# Signal_Integrity_2L.net
KiCad netlist of a schematic drawn in Altium Designer
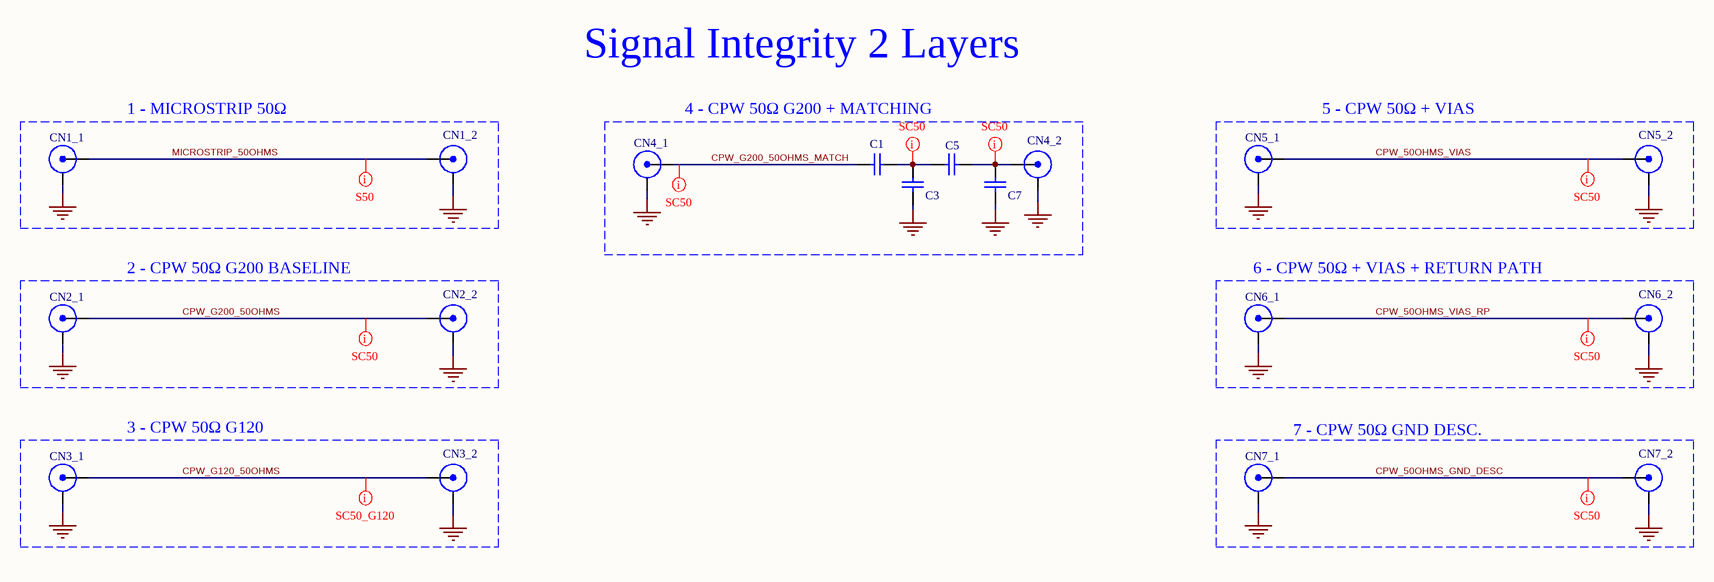
[diagram p0: Signal_Integrity_2L.SchDoc]

(export (version "E")
  (design (tool "Eeschema 10.0.6"))
  (components
    (comp (ref "C1")
      (value "CAP SMD 0402")
      (footprint "0402")
      (description "0402")
      (libsource (lib "Impedance") (part "CAP SMD 0402"))
    )
    (comp (ref "C3")
      (value "CAP SMD 0402")
      (footprint "0402")
      (description "0402")
      (libsource (lib "Impedance") (part "CAP SMD 0402"))
    )
    (comp (ref "C5")
      (value "CAP SMD 0402")
      (footprint "0402")
      (description "0402")
      (libsource (lib "Impedance") (part "CAP SMD 0402"))
    )
    (comp (ref "C7")
      (value "CAP SMD 0402")
      (footprint "0402")
      (description "0402")
      (libsource (lib "Impedance") (part "CAP SMD 0402"))
    )
    (comp (ref "CN1_1")
      (value "SMA-KE EDGE")
      (footprint "SMA-KE EDGE")
      (description "SMA Connector Receptacle, Female Socket 50Ohm Board Edge, End Launch Solder")
      (fields
        (field (name "MOUSER PART NUMBER") "712-CONSMA020.062-G")
        (field (name "MANUFACTURER_PART_NUMBER") "CONSMA020.062-G")
      )
      (libsource (lib "Impedance") (part "SMA-KE EDGE"))
    )
    (comp (ref "CN1_2")
      (value "SMA-KE EDGE")
      (footprint "SMA-KE EDGE")
      (description "SMA Connector Receptacle, Female Socket 50Ohm Board Edge, End Launch Solder")
      (fields
        (field (name "MOUSER PART NUMBER") "712-CONSMA020.062-G")
        (field (name "MANUFACTURER_PART_NUMBER") "CONSMA020.062-G")
      )
      (libsource (lib "Impedance") (part "SMA-KE EDGE"))
    )
    (comp (ref "CN2_1")
      (value "SMA-KE EDGE")
      (footprint "SMA-KE EDGE")
      (description "SMA Connector Receptacle, Female Socket 50Ohm Board Edge, End Launch Solder")
      (fields
        (field (name "MOUSER PART NUMBER") "712-CONSMA020.062-G")
        (field (name "MANUFACTURER_PART_NUMBER") "CONSMA020.062-G")
      )
      (libsource (lib "Impedance") (part "SMA-KE EDGE"))
    )
    (comp (ref "CN2_2")
      (value "SMA-KE EDGE")
      (footprint "SMA-KE EDGE")
      (description "SMA Connector Receptacle, Female Socket 50Ohm Board Edge, End Launch Solder")
      (fields
        (field (name "MOUSER PART NUMBER") "712-CONSMA020.062-G")
        (field (name "MANUFACTURER_PART_NUMBER") "CONSMA020.062-G")
      )
      (libsource (lib "Impedance") (part "SMA-KE EDGE"))
    )
    (comp (ref "CN3_1")
      (value "SMA-KE EDGE")
      (footprint "SMA-KE EDGE")
      (description "SMA Connector Receptacle, Female Socket 50Ohm Board Edge, End Launch Solder")
      (fields
        (field (name "MOUSER PART NUMBER") "712-CONSMA020.062-G")
        (field (name "MANUFACTURER_PART_NUMBER") "CONSMA020.062-G")
      )
      (libsource (lib "Impedance") (part "SMA-KE EDGE"))
    )
    (comp (ref "CN3_2")
      (value "SMA-KE EDGE")
      (footprint "SMA-KE EDGE")
      (description "SMA Connector Receptacle, Female Socket 50Ohm Board Edge, End Launch Solder")
      (fields
        (field (name "MOUSER PART NUMBER") "712-CONSMA020.062-G")
        (field (name "MANUFACTURER_PART_NUMBER") "CONSMA020.062-G")
      )
      (libsource (lib "Impedance") (part "SMA-KE EDGE"))
    )
    (comp (ref "CN4_1")
      (value "SMA-KE EDGE")
      (footprint "SMA-KE EDGE")
      (description "SMA Connector Receptacle, Female Socket 50Ohm Board Edge, End Launch Solder")
      (fields
        (field (name "MOUSER PART NUMBER") "712-CONSMA020.062-G")
        (field (name "MANUFACTURER_PART_NUMBER") "CONSMA020.062-G")
      )
      (libsource (lib "Impedance") (part "SMA-KE EDGE"))
    )
    (comp (ref "CN4_2")
      (value "SMA-KE EDGE")
      (footprint "SMA-KE EDGE")
      (description "SMA Connector Receptacle, Female Socket 50Ohm Board Edge, End Launch Solder")
      (fields
        (field (name "MOUSER PART NUMBER") "712-CONSMA020.062-G")
        (field (name "MANUFACTURER_PART_NUMBER") "CONSMA020.062-G")
      )
      (libsource (lib "Impedance") (part "SMA-KE EDGE"))
    )
    (comp (ref "CN5_1")
      (value "SMA-KE EDGE")
      (footprint "SMA-KE EDGE")
      (description "SMA Connector Receptacle, Female Socket 50Ohm Board Edge, End Launch Solder")
      (fields
        (field (name "MOUSER PART NUMBER") "712-CONSMA020.062-G")
        (field (name "MANUFACTURER_PART_NUMBER") "CONSMA020.062-G")
      )
      (libsource (lib "Impedance") (part "SMA-KE EDGE"))
    )
    (comp (ref "CN5_2")
      (value "SMA-KE EDGE")
      (footprint "SMA-KE EDGE")
      (description "SMA Connector Receptacle, Female Socket 50Ohm Board Edge, End Launch Solder")
      (fields
        (field (name "MOUSER PART NUMBER") "712-CONSMA020.062-G")
        (field (name "MANUFACTURER_PART_NUMBER") "CONSMA020.062-G")
      )
      (libsource (lib "Impedance") (part "SMA-KE EDGE"))
    )
    (comp (ref "CN6_1")
      (value "SMA-KE EDGE")
      (footprint "SMA-KE EDGE")
      (description "SMA Connector Receptacle, Female Socket 50Ohm Board Edge, End Launch Solder")
      (fields
        (field (name "MOUSER PART NUMBER") "712-CONSMA020.062-G")
        (field (name "MANUFACTURER_PART_NUMBER") "CONSMA020.062-G")
      )
      (libsource (lib "Impedance") (part "SMA-KE EDGE"))
    )
    (comp (ref "CN6_2")
      (value "SMA-KE EDGE")
      (footprint "SMA-KE EDGE")
      (description "SMA Connector Receptacle, Female Socket 50Ohm Board Edge, End Launch Solder")
      (fields
        (field (name "MOUSER PART NUMBER") "712-CONSMA020.062-G")
        (field (name "MANUFACTURER_PART_NUMBER") "CONSMA020.062-G")
      )
      (libsource (lib "Impedance") (part "SMA-KE EDGE"))
    )
    (comp (ref "CN7_1")
      (value "SMA-KE EDGE")
      (footprint "SMA-KE EDGE")
      (description "SMA Connector Receptacle, Female Socket 50Ohm Board Edge, End Launch Solder")
      (fields
        (field (name "MOUSER PART NUMBER") "712-CONSMA020.062-G")
        (field (name "MANUFACTURER_PART_NUMBER") "CONSMA020.062-G")
      )
      (libsource (lib "Impedance") (part "SMA-KE EDGE"))
    )
    (comp (ref "CN7_2")
      (value "SMA-KE EDGE")
      (footprint "SMA-KE EDGE")
      (description "SMA Connector Receptacle, Female Socket 50Ohm Board Edge, End Launch Solder")
      (fields
        (field (name "MOUSER PART NUMBER") "712-CONSMA020.062-G")
        (field (name "MANUFACTURER_PART_NUMBER") "CONSMA020.062-G")
      )
      (libsource (lib "Impedance") (part "SMA-KE EDGE"))
    )
  )
  (nets
    (net (code "1") (name "/CPW_50OHMS_GND_DESC") (class "Default")
      (node (ref "CN7_1") (pin "1") (pinfunction "SIGNAL_1") (pintype "passive"))
      (node (ref "CN7_2") (pin "1") (pinfunction "SIGNAL_1") (pintype "passive"))
    )
    (net (code "2") (name "/CPW_50OHMS_VIAS") (class "Default")
      (node (ref "CN5_1") (pin "1") (pinfunction "SIGNAL_1") (pintype "passive"))
      (node (ref "CN5_2") (pin "1") (pinfunction "SIGNAL_1") (pintype "passive"))
    )
    (net (code "3") (name "/CPW_50OHMS_VIAS_RP") (class "Default")
      (node (ref "CN6_1") (pin "1") (pinfunction "SIGNAL_1") (pintype "passive"))
      (node (ref "CN6_2") (pin "1") (pinfunction "SIGNAL_1") (pintype "passive"))
    )
    (net (code "4") (name "/CPW_G120_50OHMS") (class "Default")
      (node (ref "CN3_1") (pin "1") (pinfunction "SIGNAL_1") (pintype "passive"))
      (node (ref "CN3_2") (pin "1") (pinfunction "SIGNAL_1") (pintype "passive"))
    )
    (net (code "5") (name "/CPW_G200_50OHMS") (class "Default")
      (node (ref "CN2_1") (pin "1") (pinfunction "SIGNAL_1") (pintype "passive"))
      (node (ref "CN2_2") (pin "1") (pinfunction "SIGNAL_1") (pintype "passive"))
    )
    (net (code "6") (name "/CPW_G200_50OHMS_MATCH") (class "Default")
      (node (ref "C1") (pin "1") (pinfunction "1_1") (pintype "passive"))
      (node (ref "CN4_1") (pin "1") (pinfunction "SIGNAL_1") (pintype "passive"))
    )
    (net (code "7") (name "/MICROSTRIP_50OHMS") (class "Default")
      (node (ref "CN1_1") (pin "1") (pinfunction "SIGNAL_1") (pintype "passive"))
      (node (ref "CN1_2") (pin "1") (pinfunction "SIGNAL_1") (pintype "passive"))
    )
    (net (code "8") (name "GND1") (class "Default")
      (node (ref "CN1_1") (pin "2") (pinfunction "GND_2") (pintype "passive"))
      (node (ref "CN1_2") (pin "2") (pinfunction "GND_2") (pintype "passive"))
    )
    (net (code "9") (name "GND2") (class "Default")
      (node (ref "CN2_1") (pin "2") (pinfunction "GND_2") (pintype "passive"))
      (node (ref "CN2_2") (pin "2") (pinfunction "GND_2") (pintype "passive"))
    )
    (net (code "10") (name "GND3") (class "Default")
      (node (ref "CN3_1") (pin "2") (pinfunction "GND_2") (pintype "passive"))
      (node (ref "CN3_2") (pin "2") (pinfunction "GND_2") (pintype "passive"))
    )
    (net (code "11") (name "GND4") (class "Default")
      (node (ref "C3") (pin "1") (pinfunction "1_1") (pintype "passive"))
      (node (ref "C7") (pin "1") (pinfunction "1_1") (pintype "passive"))
      (node (ref "CN4_1") (pin "2") (pinfunction "GND_2") (pintype "passive"))
      (node (ref "CN4_2") (pin "2") (pinfunction "GND_2") (pintype "passive"))
    )
    (net (code "12") (name "GND5") (class "Default")
      (node (ref "CN5_1") (pin "2") (pinfunction "GND_2") (pintype "passive"))
      (node (ref "CN5_2") (pin "2") (pinfunction "GND_2") (pintype "passive"))
    )
    (net (code "13") (name "GND6") (class "Default")
      (node (ref "CN6_1") (pin "2") (pinfunction "GND_2") (pintype "passive"))
      (node (ref "CN6_2") (pin "2") (pinfunction "GND_2") (pintype "passive"))
    )
    (net (code "14") (name "GND7") (class "Default")
      (node (ref "CN7_1") (pin "2") (pinfunction "GND_2") (pintype "passive"))
      (node (ref "CN7_2") (pin "2") (pinfunction "GND_2") (pintype "passive"))
    )
    (net (code "15") (name "Net-(C1-Pad2)") (class "Default")
      (node (ref "C1") (pin "2") (pinfunction "2_2") (pintype "passive"))
      (node (ref "C3") (pin "2") (pinfunction "2_2") (pintype "passive"))
      (node (ref "C5") (pin "1") (pinfunction "1_1") (pintype "passive"))
    )
    (net (code "16") (name "Net-(CN4_2-SIGNAL)") (class "Default")
      (node (ref "C5") (pin "2") (pinfunction "2_2") (pintype "passive"))
      (node (ref "C7") (pin "2") (pinfunction "2_2") (pintype "passive"))
      (node (ref "CN4_2") (pin "1") (pinfunction "SIGNAL_1") (pintype "passive"))
    )
  )
)
